# easyeda-doit-devkit-v1.net
KiCad netlist of a schematic drawn in EasyEDA
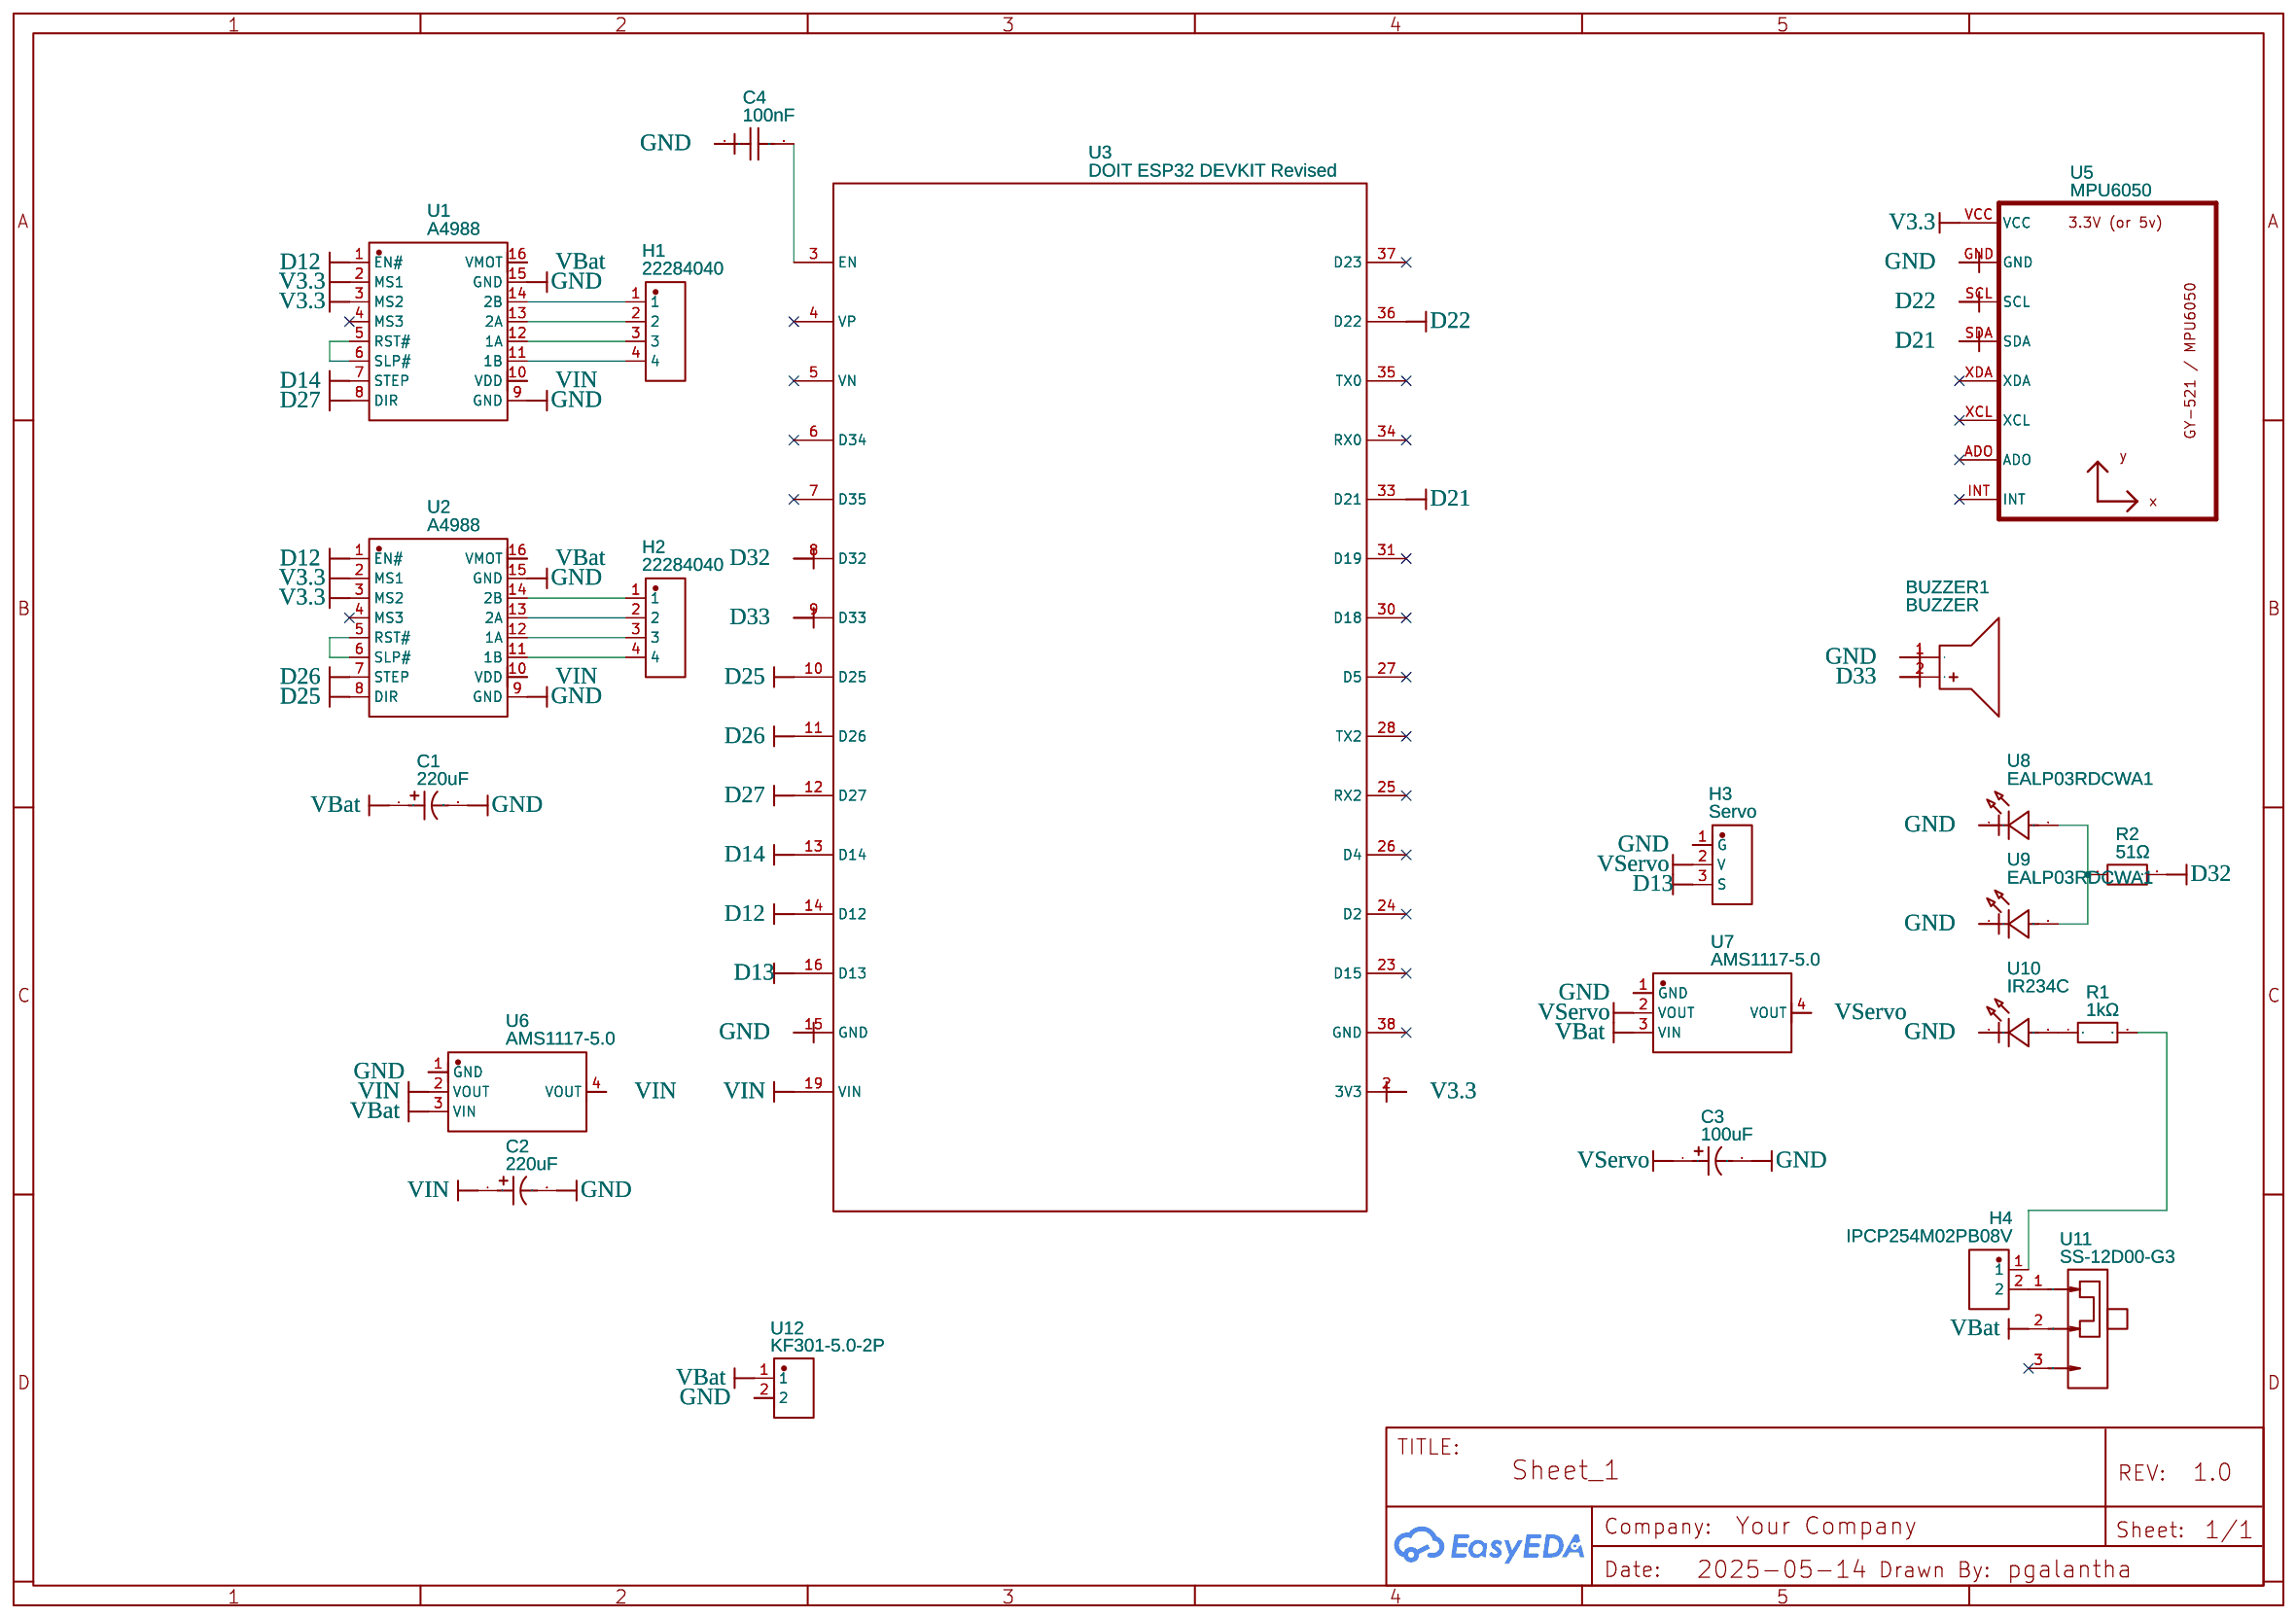
[diagram p0: schematic sheet]

(export (version "E")
  (design (tool "Eeschema 10.0.6"))
  (components
    (comp (ref "BUZZER1")
      (value "BUZZER")
      (fields (field (name "Manufacturer Part") "buzzer"))
      (libsource (lib "") (part "BUZZER"))
    )
    (comp (ref "C1")
      (value "220uF")
      (fields (field (name "Manufacturer Part") "SY221M016E070A") (field (name "Manufacturer") "CapXon(丰宾)"))
      (libsource (lib "") (part "SY221M016E070A"))
    )
    (comp (ref "C2")
      (value "220uF")
      (fields (field (name "Manufacturer Part") "SY221M016E070A") (field (name "Manufacturer") "CapXon(丰宾)"))
      (libsource (lib "") (part "SY221M016E070A_1"))
    )
    (comp (ref "C3")
      (value "100uF")
      (fields (field (name "Manufacturer Part") "16V100uF CD288") (field (name "Manufacturer") "HRK(鸿瑞凯电子)"))
      (libsource (lib "") (part "16V100UF CD288"))
    )
    (comp (ref "C4")
      (value "100nF")
      (fields
        (field (name "Manufacturer Part") "CC1H104MC1FD3F6C10MF")
        (field (name "Manufacturer") "Dersonic(德尔创)")
      )
      (libsource (lib "") (part "CC1H104MC1FD3F6C10MF"))
    )
    (comp (ref "H1")
      (value "22284040")
      (fields (field (name "Manufacturer") "MOLEX"))
      (libsource (lib "") (part "22284040"))
    )
    (comp (ref "H2")
      (value "22284040")
      (fields (field (name "Manufacturer") "MOLEX"))
      (libsource (lib "") (part "22284040"))
    )
    (comp (ref "H3")
      (value "Servo")
      (fields (field (name "Manufacturer Part") "22284035") (field (name "Manufacturer") "MOLEX"))
      (libsource (lib "") (part "22284035"))
    )
    (comp (ref "H4")
      (value "IPCP254M02PB08V")
      (fields (field (name "Manufacturer") "INCP"))
      (libsource (lib "") (part "IPCP254M02PB08V"))
    )
    (comp (ref "R1")
      (value "1kΩ")
      (fields (field (name "Manufacturer Part") "RN1WS1KΩFT/BA1") (field (name "Manufacturer") "Tyohm(幸亚电阻)"))
      (libsource (lib "") (part "RN1WS1KΩFT/BA1"))
    )
    (comp (ref "R2")
      (value "51Ω")
      (fields
        (field (name "Manufacturer Part") "RN 1/2W 51R F T/B A1")
        (field (name "Manufacturer") "Tyohm(幸亚电阻)")
      )
      (libsource (lib "") (part "RN 1/2W 51R F T/B A1"))
    )
    (comp (ref "U1") (value "A4988") (libsource (lib "") (part "A4988")))
    (comp (ref "U2") (value "A4988") (libsource (lib "") (part "A4988")))
    (comp (ref "U3")
      (value "DOIT ESP32 DEVKIT Revised")
      (fields
        (field (name "Manufacturer Part") "M103QH3200PH3Q0")
        (field (name "Manufacturer") "Espressif Systems")
      )
      (libsource (lib "") (part "DOIT ESP32 DEVKIT Revised"))
    )
    (comp (ref "U5") (value "MPU6050") (libsource (lib "") (part "MPU6050")))
    (comp (ref "U6")
      (value "AMS1117-5.0")
      (fields (field (name "Manufacturer") "AMS"))
      (libsource (lib "") (part "AMS1117-5.0"))
    )
    (comp (ref "U7")
      (value "AMS1117-5.0")
      (fields (field (name "Manufacturer") "AMS"))
      (libsource (lib "") (part "AMS1117-5.0"))
    )
    (comp (ref "U8")
      (value "EALP03RDCWA1")
      (fields (field (name "Manufacturer") "EVERLIGHT(亿光)"))
      (libsource (lib "") (part "EALP03RDCWA1"))
    )
    (comp (ref "U9")
      (value "EALP03RDCWA1")
      (fields (field (name "Manufacturer") "EVERLIGHT(亿光)"))
      (libsource (lib "") (part "EALP03RDCWA1"))
    )
    (comp (ref "U10")
      (value "IR234C")
      (fields (field (name "Manufacturer") "EVERLIGHT(亿光)"))
      (libsource (lib "") (part "IR234C"))
    )
    (comp (ref "U11")
      (value "SS-12D00-G3")
      (fields (field (name "Manufacturer") "SOFNG(硕方)"))
      (libsource (lib "") (part "SS-12D00-G3"))
    )
    (comp (ref "U12")
      (value "KF301-5.0-2P")
      (fields (field (name "Manufacturer") "KEFA(科发)"))
      (libsource (lib "") (part "KF301-5.0-2P"))
    )
  )
  (nets
    (net (code "1") (name "D12") (class "Default")
      (node (ref "U1") (pin "1") (pinfunction "EN#_1") (pintype "unspecified"))
      (node (ref "U2") (pin "1") (pinfunction "EN#_1") (pintype "unspecified"))
      (node (ref "U3") (pin "14") (pinfunction "D12_14") (pintype "bidirectional"))
    )
    (net (code "2") (name "D13") (class "Default")
      (node (ref "H3") (pin "3") (pinfunction "S_3") (pintype "unspecified"))
      (node (ref "U3") (pin "16") (pinfunction "D13_16") (pintype "bidirectional"))
    )
    (net (code "3") (name "D14") (class "Default")
      (node (ref "U1") (pin "7") (pinfunction "STEP_7") (pintype "unspecified"))
      (node (ref "U3") (pin "13") (pinfunction "D14_13") (pintype "bidirectional"))
    )
    (net (code "4") (name "D21") (class "Default")
      (node (ref "U3") (pin "33") (pinfunction "D21_33") (pintype "bidirectional"))
      (node (ref "U5") (pin "SDA") (pinfunction "SDA_SDA") (pintype "bidirectional"))
    )
    (net (code "5") (name "D22") (class "Default")
      (node (ref "U3") (pin "36") (pinfunction "D22_36") (pintype "bidirectional"))
      (node (ref "U5") (pin "SCL") (pinfunction "SCL_SCL") (pintype "bidirectional"))
    )
    (net (code "6") (name "D25") (class "Default")
      (node (ref "U2") (pin "8") (pinfunction "DIR_8") (pintype "unspecified"))
      (node (ref "U3") (pin "10") (pinfunction "D25_10") (pintype "bidirectional"))
    )
    (net (code "7") (name "D26") (class "Default")
      (node (ref "U2") (pin "7") (pinfunction "STEP_7") (pintype "unspecified"))
      (node (ref "U3") (pin "11") (pinfunction "D26_11") (pintype "bidirectional"))
    )
    (net (code "8") (name "D27") (class "Default")
      (node (ref "U1") (pin "8") (pinfunction "DIR_8") (pintype "unspecified"))
      (node (ref "U3") (pin "12") (pinfunction "D27_12") (pintype "passive"))
    )
    (net (code "9") (name "D32") (class "Default")
      (node (ref "R2") (pin "2") (pinfunction "2_2") (pintype "unspecified"))
      (node (ref "U3") (pin "8") (pinfunction "D32_8") (pintype "bidirectional"))
    )
    (net (code "10") (name "D33") (class "Default")
      (node (ref "BUZZER1") (pin "2") (pinfunction "+_2") (pintype "unspecified"))
      (node (ref "U3") (pin "9") (pinfunction "D33_9") (pintype "bidirectional"))
    )
    (net (code "11") (name "GND") (class "Default")
      (node (ref "BUZZER1") (pin "1") (pinfunction "-_1") (pintype "unspecified"))
      (node (ref "C1") (pin "2") (pinfunction "2_2") (pintype "input"))
      (node (ref "C2") (pin "2") (pinfunction "2_2") (pintype "input"))
      (node (ref "C3") (pin "2") (pinfunction "2_2") (pintype "input"))
      (node (ref "C4") (pin "1") (pinfunction "1_1") (pintype "unspecified"))
      (node (ref "H3") (pin "1") (pinfunction "G_1") (pintype "unspecified"))
      (node (ref "U1") (pin "15") (pinfunction "GND_15") (pintype "unspecified"))
      (node (ref "U1") (pin "9") (pinfunction "GND_9") (pintype "unspecified"))
      (node (ref "U10") (pin "1") (pinfunction "C_1") (pintype "unspecified"))
      (node (ref "U12") (pin "2") (pinfunction "2_2") (pintype "unspecified"))
      (node (ref "U2") (pin "15") (pinfunction "GND_15") (pintype "unspecified"))
      (node (ref "U2") (pin "9") (pinfunction "GND_9") (pintype "unspecified"))
      (node (ref "U3") (pin "15") (pinfunction "GND_15") (pintype "passive"))
      (node (ref "U5") (pin "GND") (pinfunction "GND_GND") (pintype "bidirectional"))
      (node (ref "U6") (pin "1") (pinfunction "GND_1") (pintype "unspecified"))
      (node (ref "U7") (pin "1") (pinfunction "GND_1") (pintype "unspecified"))
      (node (ref "U8") (pin "1") (pinfunction "K_1") (pintype "unspecified"))
      (node (ref "U9") (pin "1") (pinfunction "K_1") (pintype "unspecified"))
    )
    (net (code "12") (name "Net-(H4-Pad1)") (class "Default")
      (node (ref "H4") (pin "1") (pinfunction "1_1") (pintype "unspecified"))
      (node (ref "R1") (pin "2") (pinfunction "2_2") (pintype "unspecified"))
    )
    (net (code "13") (name "Net-(H4-Pad2)") (class "Default")
      (node (ref "H4") (pin "2") (pinfunction "2_2") (pintype "unspecified"))
      (node (ref "U11") (pin "1") (pinfunction "1_1") (pintype "unspecified"))
    )
    (net (code "14") (name "Net-(U1-1A)") (class "Default")
      (node (ref "H1") (pin "3") (pinfunction "3_3") (pintype "unspecified"))
      (node (ref "U1") (pin "12") (pinfunction "1A_12") (pintype "unspecified"))
    )
    (net (code "15") (name "Net-(U1-1B)") (class "Default")
      (node (ref "H1") (pin "4") (pinfunction "4_4") (pintype "unspecified"))
      (node (ref "U1") (pin "11") (pinfunction "1B_11") (pintype "unspecified"))
    )
    (net (code "16") (name "Net-(U1-2A)") (class "Default")
      (node (ref "H1") (pin "2") (pinfunction "2_2") (pintype "unspecified"))
      (node (ref "U1") (pin "13") (pinfunction "2A_13") (pintype "unspecified"))
    )
    (net (code "17") (name "Net-(U1-2B)") (class "Default")
      (node (ref "H1") (pin "1") (pinfunction "1_1") (pintype "unspecified"))
      (node (ref "U1") (pin "14") (pinfunction "2B_14") (pintype "unspecified"))
    )
    (net (code "18") (name "Net-(U1-RST#)") (class "Default")
      (node (ref "U1") (pin "5") (pinfunction "RST#_5") (pintype "unspecified"))
      (node (ref "U1") (pin "6") (pinfunction "SLP#_6") (pintype "unspecified"))
    )
    (net (code "19") (name "Net-(U2-1A)") (class "Default")
      (node (ref "H2") (pin "3") (pinfunction "3_3") (pintype "unspecified"))
      (node (ref "U2") (pin "12") (pinfunction "1A_12") (pintype "unspecified"))
    )
    (net (code "20") (name "Net-(U2-1B)") (class "Default")
      (node (ref "H2") (pin "4") (pinfunction "4_4") (pintype "unspecified"))
      (node (ref "U2") (pin "11") (pinfunction "1B_11") (pintype "unspecified"))
    )
    (net (code "21") (name "Net-(U2-2A)") (class "Default")
      (node (ref "H2") (pin "2") (pinfunction "2_2") (pintype "unspecified"))
      (node (ref "U2") (pin "13") (pinfunction "2A_13") (pintype "unspecified"))
    )
    (net (code "22") (name "Net-(U2-2B)") (class "Default")
      (node (ref "H2") (pin "1") (pinfunction "1_1") (pintype "unspecified"))
      (node (ref "U2") (pin "14") (pinfunction "2B_14") (pintype "unspecified"))
    )
    (net (code "23") (name "Net-(U2-RST#)") (class "Default")
      (node (ref "U2") (pin "5") (pinfunction "RST#_5") (pintype "unspecified"))
      (node (ref "U2") (pin "6") (pinfunction "SLP#_6") (pintype "unspecified"))
    )
    (net (code "24") (name "Net-(U3-EN)") (class "Default")
      (node (ref "C4") (pin "2") (pinfunction "2_2") (pintype "unspecified"))
      (node (ref "U3") (pin "3") (pinfunction "EN_3") (pintype "input"))
    )
    (net (code "25") (name "Net-(U8-A)") (class "Default")
      (node (ref "R2") (pin "1") (pinfunction "1_1") (pintype "unspecified"))
      (node (ref "U8") (pin "2") (pinfunction "A_2") (pintype "unspecified"))
      (node (ref "U9") (pin "2") (pinfunction "A_2") (pintype "unspecified"))
    )
    (net (code "26") (name "Net-(U10-A)") (class "Default")
      (node (ref "R1") (pin "1") (pinfunction "1_1") (pintype "unspecified"))
      (node (ref "U10") (pin "2") (pinfunction "A_2") (pintype "unspecified"))
    )
    (net (code "27") (name "V3.3") (class "Default")
      (node (ref "U1") (pin "2") (pinfunction "MS1_2") (pintype "unspecified"))
      (node (ref "U1") (pin "3") (pinfunction "MS2_3") (pintype "unspecified"))
      (node (ref "U2") (pin "2") (pinfunction "MS1_2") (pintype "unspecified"))
      (node (ref "U2") (pin "3") (pinfunction "MS2_3") (pintype "unspecified"))
      (node (ref "U3") (pin "2") (pinfunction "3V3_2") (pintype "passive"))
      (node (ref "U5") (pin "VCC") (pinfunction "VCC_VCC") (pintype "bidirectional"))
    )
    (net (code "28") (name "VBat") (class "Default")
      (node (ref "C1") (pin "1") (pinfunction "1_1") (pintype "input"))
      (node (ref "U1") (pin "16") (pinfunction "VMOT_16") (pintype "unspecified"))
      (node (ref "U11") (pin "2") (pinfunction "2_2") (pintype "unspecified"))
      (node (ref "U12") (pin "1") (pinfunction "1_1") (pintype "unspecified"))
      (node (ref "U2") (pin "16") (pinfunction "VMOT_16") (pintype "unspecified"))
      (node (ref "U6") (pin "3") (pinfunction "VIN_3") (pintype "unspecified"))
      (node (ref "U7") (pin "3") (pinfunction "VIN_3") (pintype "unspecified"))
    )
    (net (code "29") (name "VIN") (class "Default")
      (node (ref "C2") (pin "1") (pinfunction "1_1") (pintype "input"))
      (node (ref "U1") (pin "10") (pinfunction "VDD_10") (pintype "unspecified"))
      (node (ref "U2") (pin "10") (pinfunction "VDD_10") (pintype "unspecified"))
      (node (ref "U3") (pin "19") (pinfunction "VIN_19") (pintype "passive"))
      (node (ref "U6") (pin "2") (pinfunction "VOUT_2") (pintype "unspecified"))
      (node (ref "U6") (pin "4") (pinfunction "VOUT_4") (pintype "unspecified"))
    )
    (net (code "30") (name "VServo") (class "Default")
      (node (ref "C3") (pin "1") (pinfunction "1_1") (pintype "input"))
      (node (ref "H3") (pin "2") (pinfunction "V_2") (pintype "unspecified"))
      (node (ref "U7") (pin "2") (pinfunction "VOUT_2") (pintype "unspecified"))
      (node (ref "U7") (pin "4") (pinfunction "VOUT_4") (pintype "unspecified"))
    )
    (net (code "31") (name "unconnected-(U1-MS3-Pad4)") (class "Default")
      (node (ref "U1") (pin "4") (pinfunction "MS3_4") (pintype "unspecified+no_connect"))
    )
    (net (code "32") (name "unconnected-(U2-MS3-Pad4)") (class "Default")
      (node (ref "U2") (pin "4") (pinfunction "MS3_4") (pintype "unspecified+no_connect"))
    )
    (net (code "33") (name "unconnected-(U3-D2-Pad24)") (class "Default")
      (node (ref "U3") (pin "24") (pinfunction "D2_24") (pintype "bidirectional+no_connect"))
    )
    (net (code "34") (name "unconnected-(U3-D4-Pad26)") (class "Default")
      (node (ref "U3") (pin "26") (pinfunction "D4_26") (pintype "bidirectional+no_connect"))
    )
    (net (code "35") (name "unconnected-(U3-D5-Pad27)") (class "Default")
      (node (ref "U3") (pin "27") (pinfunction "D5_27") (pintype "bidirectional+no_connect"))
    )
    (net (code "36") (name "unconnected-(U3-D15-Pad23)") (class "Default")
      (node (ref "U3") (pin "23") (pinfunction "D15_23") (pintype "bidirectional+no_connect"))
    )
    (net (code "37") (name "unconnected-(U3-D18-Pad30)") (class "Default")
      (node (ref "U3") (pin "30") (pinfunction "D18_30") (pintype "bidirectional+no_connect"))
    )
    (net (code "38") (name "unconnected-(U3-D19-Pad31)") (class "Default")
      (node (ref "U3") (pin "31") (pinfunction "D19_31") (pintype "bidirectional+no_connect"))
    )
    (net (code "39") (name "unconnected-(U3-D23-Pad37)") (class "Default")
      (node (ref "U3") (pin "37") (pinfunction "D23_37") (pintype "bidirectional+no_connect"))
    )
    (net (code "40") (name "unconnected-(U3-D34-Pad6)") (class "Default")
      (node (ref "U3") (pin "6") (pinfunction "D34_6") (pintype "input+no_connect"))
    )
    (net (code "41") (name "unconnected-(U3-D35-Pad7)") (class "Default")
      (node (ref "U3") (pin "7") (pinfunction "D35_7") (pintype "input+no_connect"))
    )
    (net (code "42") (name "unconnected-(U3-GND-Pad38)") (class "Default")
      (node (ref "U3") (pin "38") (pinfunction "GND_38") (pintype "passive+no_connect"))
    )
    (net (code "43") (name "unconnected-(U3-RX0-Pad34)") (class "Default")
      (node (ref "U3") (pin "34") (pinfunction "RX0_34") (pintype "bidirectional+no_connect"))
    )
    (net (code "44") (name "unconnected-(U3-RX2-Pad25)") (class "Default")
      (node (ref "U3") (pin "25") (pinfunction "RX2_25") (pintype "bidirectional+no_connect"))
    )
    (net (code "45") (name "unconnected-(U3-TX0-Pad35)") (class "Default")
      (node (ref "U3") (pin "35") (pinfunction "TX0_35") (pintype "bidirectional+no_connect"))
    )
    (net (code "46") (name "unconnected-(U3-TX2-Pad28)") (class "Default")
      (node (ref "U3") (pin "28") (pinfunction "TX2_28") (pintype "bidirectional+no_connect"))
    )
    (net (code "47") (name "unconnected-(U3-VN-Pad5)") (class "Default")
      (node (ref "U3") (pin "5") (pinfunction "VN_5") (pintype "input+no_connect"))
    )
    (net (code "48") (name "unconnected-(U3-VP-Pad4)") (class "Default")
      (node (ref "U3") (pin "4") (pinfunction "VP_4") (pintype "input+no_connect"))
    )
    (net (code "49") (name "unconnected-(U5-PadADO)") (class "Default")
      (node (ref "U5") (pin "ADO") (pinfunction "ADO_ADO") (pintype "bidirectional+no_connect"))
    )
    (net (code "50") (name "unconnected-(U5-PadINT)") (class "Default")
      (node (ref "U5") (pin "INT") (pinfunction "INT_INT") (pintype "bidirectional+no_connect"))
    )
    (net (code "51") (name "unconnected-(U5-PadXCL)") (class "Default")
      (node (ref "U5") (pin "XCL") (pinfunction "XCL_XCL") (pintype "bidirectional+no_connect"))
    )
    (net (code "52") (name "unconnected-(U5-PadXDA)") (class "Default")
      (node (ref "U5") (pin "XDA") (pinfunction "XDA_XDA") (pintype "bidirectional+no_connect"))
    )
    (net (code "53") (name "unconnected-(U11-Pad3)") (class "Default")
      (node (ref "U11") (pin "3") (pinfunction "3_3") (pintype "unspecified+no_connect"))
    )
  )
)
